# tricorder-teensy-mk-1_12_2.net
KiCad netlist of a schematic drawn in EAGLE
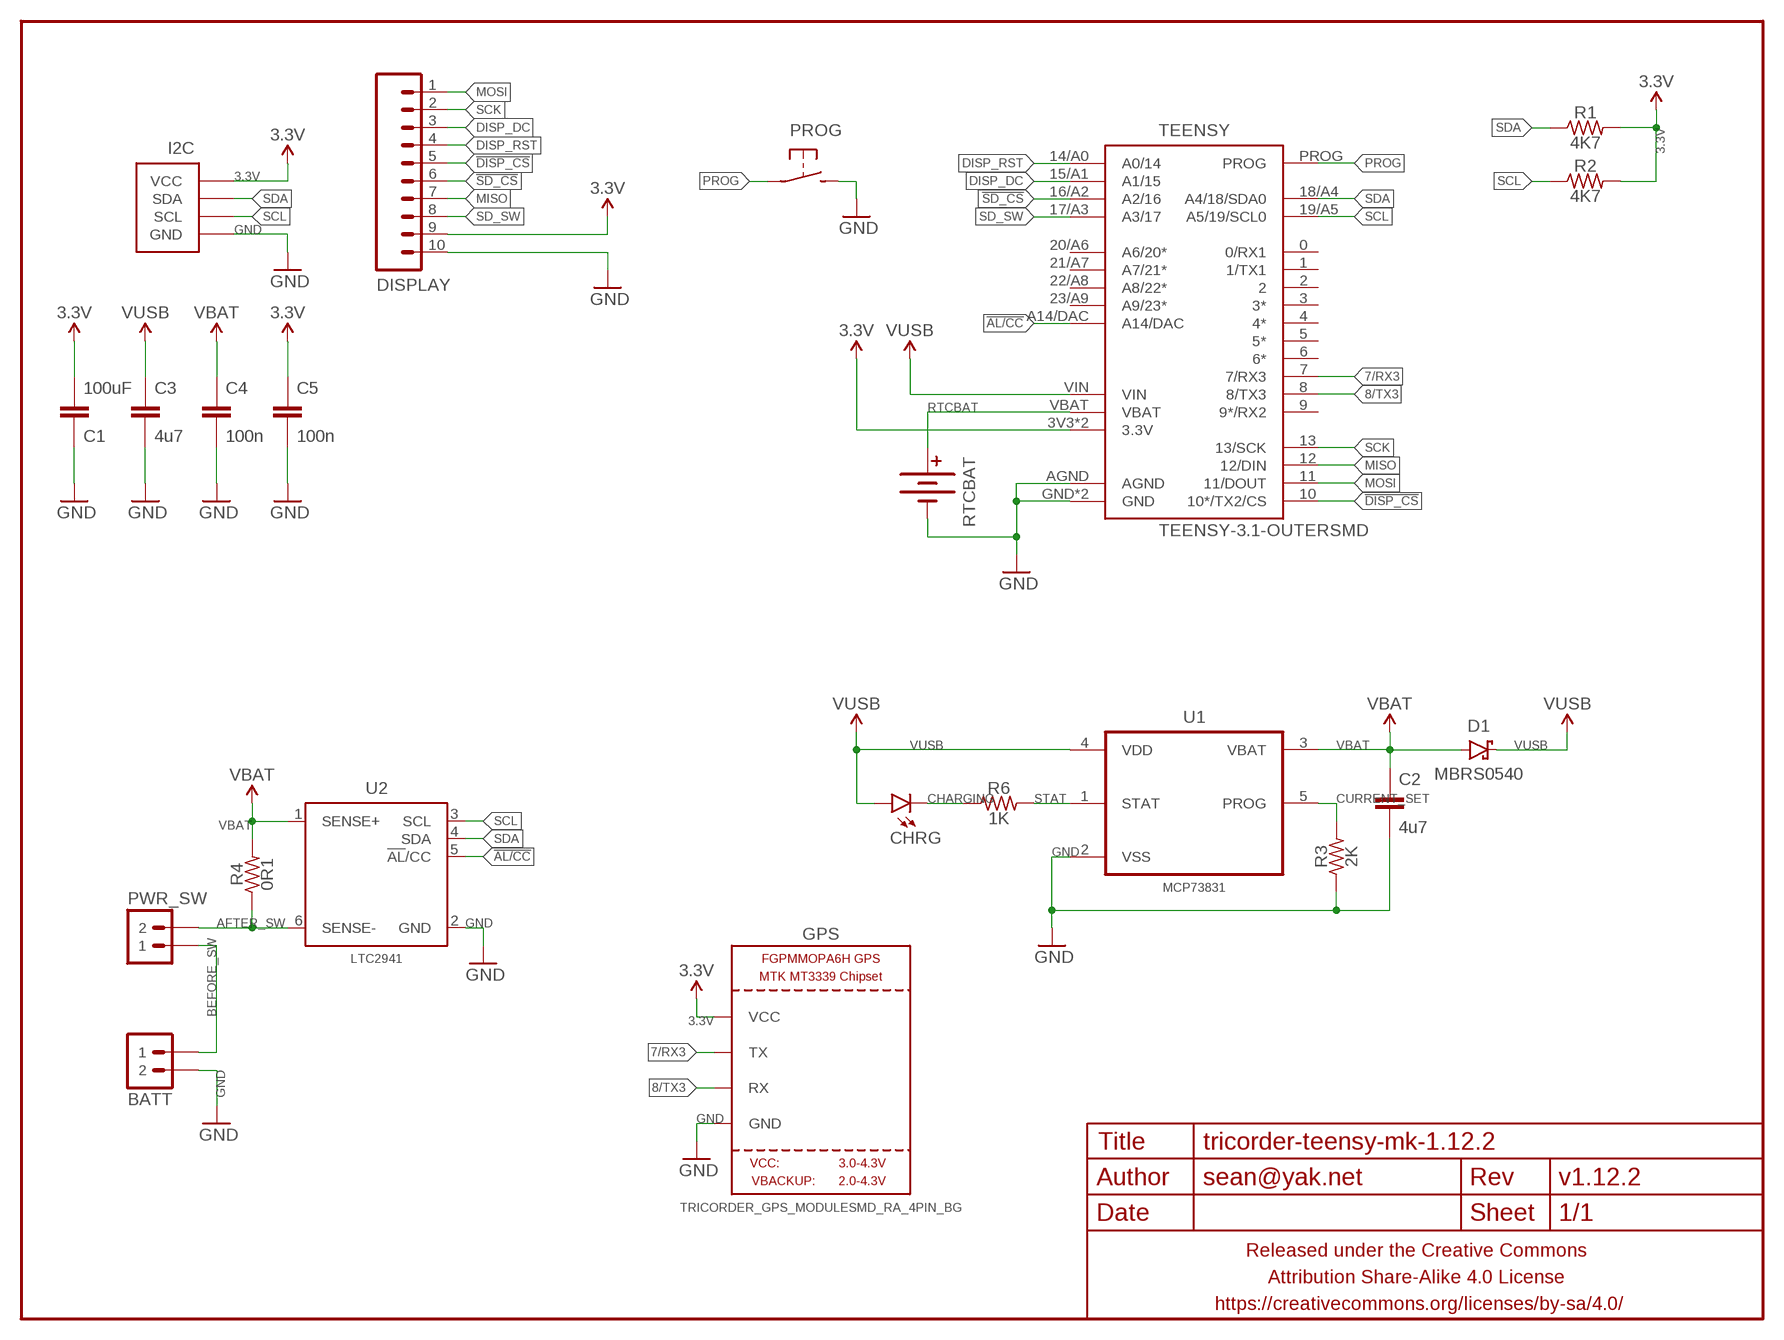
[diagram p0: schematic, sheet 1]

(export (version "E")
  (design (tool "Eeschema 10.0.6"))
  (components
    (comp (ref "BATT")
      (value "M02JST-2MM-SMT")
      (footprint "eagle-import:JST-2-SMD")
      (libsource (lib "eagle-import") (part "M02JST-2MM-SMT"))
    )
    (comp (ref "C1")
      (value "100uF")
      (footprint "eagle-import:C1210")
      (libsource (lib "eagle-import") (part "CAPACITOR-CERAMICC1210"))
    )
    (comp (ref "C2")
      (value "4u7")
      (footprint "eagle-import:C0603-TIGHTER")
      (libsource (lib "eagle-import") (part "CAPACITOR-CERAMICC0603-TIGHTER"))
    )
    (comp (ref "C3")
      (value "4u7")
      (footprint "eagle-import:C0603-TIGHTER")
      (libsource (lib "eagle-import") (part "CAPACITOR-CERAMICC0603-TIGHTER"))
    )
    (comp (ref "C4")
      (value "100n")
      (footprint "eagle-import:C0603-TIGHTER")
      (libsource (lib "eagle-import") (part "CAPACITOR-CERAMICC0603-TIGHTER"))
    )
    (comp (ref "C5")
      (value "100n")
      (footprint "eagle-import:C0603-TIGHTER")
      (libsource (lib "eagle-import") (part "CAPACITOR-CERAMICC0603-TIGHTER"))
    )
    (comp (ref "CHRG")
      (value "LED0603-TIGHT")
      (footprint "eagle-import:LED-0603-TIGHT")
      (libsource (lib "eagle-import") (part "LED0603-TIGHT"))
    )
    (comp (ref "D1")
      (value "MBRS0540")
      (footprint "eagle-import:SOD123-SCHOTTKY")
      (libsource (lib "eagle-import") (part "DIODE-SCHOTTKYSOD123"))
    )
    (comp (ref "DISPLAY")
      (value "M10SMD_RA_2MM")
      (footprint "eagle-import:1X10_SMD_RA_MALE")
      (libsource (lib "eagle-import") (part "M10SMD_RA_2MM"))
    )
    (comp (ref "FRAME1")
      (value "FRAME-LETTERNO_PACKAGE")
      (footprint "eagle-import:DUMMY")
      (fields
        (field (name "DESIGNER") "sean@yak.net")
        (field (name "VERSION") "v1.12.2")
        (field (name "DESIGNER_1") "sean@yak.net")
        (field (name "VERSION_1") "v1.12.2")
      )
      (libsource (lib "eagle-import") (part "FRAME-LETTERNO_PACKAGE"))
    )
    (comp (ref "GPS")
      (value "TRICORDER_GPS_MODULESMD_RA_4PIN_BG")
      (footprint "eagle-import:TRICORDER_GPS_MODULE_RA_CONN_SMD_4PIN_BG")
      (libsource (lib "eagle-import") (part "TRICORDER_GPS_MODULESMD_RA_4PIN_BG"))
    )
    (comp (ref "I2C")
      (value "M04-I2CSMD_2MM_RA")
      (footprint "eagle-import:1X04_SMD_RA_2MM_I2C")
      (libsource (lib "eagle-import") (part "M04-I2CSMD_2MM_RA"))
    )
    (comp (ref "PROG")
      (value "SPST-NO-TACTCK-PTS840-GK")
      (footprint "eagle-import:TACTILE-SMD-CK-PTS840-GK")
      (libsource (lib "eagle-import") (part "SPST-NO-TACTCK-PTS840-GK"))
    )
    (comp (ref "PWR_SW")
      (value "M02JST-2MM-SMT")
      (footprint "eagle-import:JST-2-SMD")
      (libsource (lib "eagle-import") (part "M02JST-2MM-SMT"))
    )
    (comp (ref "R1")
      (value "4K7")
      (footprint "eagle-import:R0603-TIGHTER")
      (libsource (lib "eagle-import") (part "RESISTORR0603-TIGHTER"))
    )
    (comp (ref "R2")
      (value "4K7")
      (footprint "eagle-import:R0603-TIGHTER")
      (libsource (lib "eagle-import") (part "RESISTORR0603-TIGHTER"))
    )
    (comp (ref "R3")
      (value "2K")
      (footprint "eagle-import:R0603-TIGHTER")
      (libsource (lib "eagle-import") (part "RESISTORR0603-TIGHTER"))
    )
    (comp (ref "R4")
      (value "0R1")
      (footprint "eagle-import:R0805-TIGHTER")
      (libsource (lib "eagle-import") (part "RESISTORR0805-TIGHTER"))
    )
    (comp (ref "R6")
      (value "1K")
      (footprint "eagle-import:R0603-TIGHTER")
      (libsource (lib "eagle-import") (part "RESISTORR0603-TIGHTER"))
    )
    (comp (ref "RTCBAT")
      (value "BATTERYML414")
      (footprint "eagle-import:BATTCON_4.8MM")
      (libsource (lib "eagle-import") (part "BATTERYML414"))
    )
    (comp (ref "TEENSY")
      (value "TEENSY-3.1-OUTERSMD")
      (footprint "eagle-import:TEENSY-3.1_SMT_BOTTOM_OUTERONLY")
      (libsource (lib "eagle-import") (part "TEENSY-3.1-OUTERSMD"))
    )
    (comp (ref "U1")
      (value "MCP73831")
      (footprint "eagle-import:SOT95P280X145-5N")
      (fields (field (name "MPN") "MCP73831T-2ACI/OT"))
      (libsource (lib "eagle-import") (part "MCP73831T-2ACI/OT"))
    )
    (comp (ref "U2")
      (value "LTC2941")
      (footprint "eagle-import:DFN200X300X50-7N")
      (libsource (lib "eagle-import") (part "LTC2941/2DCB"))
    )
  )
  (nets
    (net (code "1") (name "/AFTER_SW") (class "Default")
      (node (ref "PWR_SW") (pin "1") (pinfunction "2_1") (pintype "passive"))
      (node (ref "R4") (pin "1") (pinfunction "1_1") (pintype "passive"))
      (node (ref "U2") (pin "6") (pinfunction "SENSE-_6") (pintype "bidirectional"))
    )
    (net (code "2") (name "/BEFORE_SW") (class "Default")
      (node (ref "BATT") (pin "2") (pinfunction "1_2") (pintype "passive"))
      (node (ref "PWR_SW") (pin "2") (pinfunction "1_2") (pintype "passive"))
    )
    (net (code "3") (name "/CHARGING") (class "Default")
      (node (ref "CHRG") (pin "C") (pinfunction "C_C") (pintype "passive"))
      (node (ref "R6") (pin "1") (pinfunction "1_1") (pintype "passive"))
    )
    (net (code "4") (name "/CURRENT_SET") (class "Default")
      (node (ref "R3") (pin "2") (pinfunction "2_2") (pintype "passive"))
      (node (ref "U1") (pin "5") (pinfunction "PROG_5") (pintype "input"))
    )
    (net (code "5") (name "/RTCBAT") (class "Default")
      (node (ref "RTCBAT") (pin "A1") (pinfunction "+_A1") (pintype "power_in"))
      (node (ref "RTCBAT") (pin "A2") (pinfunction "+_A2") (pintype "power_in"))
      (node (ref "TEENSY") (pin "VBAT") (pinfunction "VBAT_VBAT") (pintype "bidirectional"))
    )
    (net (code "6") (name "/STAT") (class "Default")
      (node (ref "R6") (pin "2") (pinfunction "2_2") (pintype "passive"))
      (node (ref "U1") (pin "1") (pinfunction "STAT_1") (pintype "output"))
    )
    (net (code "7") (name "/~{AL{slash}CC}") (class "Default")
      (node (ref "TEENSY") (pin "A14/DAC") (pinfunction "A14/DAC_A14/DAC") (pintype "bidirectional"))
      (node (ref "U2") (pin "5") (pinfunction "~{AL}/CC_5") (pintype "bidirectional"))
    )
    (net (code "8") (name "/~{DISP_CS}") (class "Default")
      (node (ref "DISPLAY") (pin "5") (pinfunction "5_5") (pintype "passive"))
      (node (ref "TEENSY") (pin "10") (pinfunction "10*/TX2/CS_10") (pintype "bidirectional"))
    )
    (net (code "9") (name "/~{SD_CS}") (class "Default")
      (node (ref "DISPLAY") (pin "6") (pinfunction "6_6") (pintype "passive"))
      (node (ref "TEENSY") (pin "16/A2") (pinfunction "A2/16_16/A2") (pintype "bidirectional"))
    )
    (net (code "10") (name "3.3V") (class "Default")
      (node (ref "C1") (pin "2") (pinfunction "2_2") (pintype "passive"))
      (node (ref "C5") (pin "1") (pinfunction "1_1") (pintype "passive"))
      (node (ref "DISPLAY") (pin "9") (pinfunction "9_9") (pintype "passive"))
      (node (ref "GPS") (pin "VCC") (pinfunction "VCC_VCC") (pintype "bidirectional"))
      (node (ref "I2C") (pin "VCC") (pinfunction "VCC_VCC") (pintype "bidirectional"))
      (node (ref "R1") (pin "2") (pinfunction "2_2") (pintype "passive"))
      (node (ref "R2") (pin "2") (pinfunction "2_2") (pintype "passive"))
      (node (ref "TEENSY") (pin "3V3") (pinfunction "3.3V_3V3") (pintype "bidirectional"))
      (node (ref "TEENSY") (pin "3V3@1") (pinfunction "3.3V_3V3@1") (pintype "bidirectional"))
    )
    (net (code "11") (name "7{slash}RX3") (class "Default")
      (node (ref "GPS") (pin "TX") (pinfunction "TX_TX") (pintype "bidirectional"))
      (node (ref "TEENSY") (pin "7") (pinfunction "7/RX3_7") (pintype "bidirectional"))
    )
    (net (code "12") (name "8{slash}TX3") (class "Default")
      (node (ref "GPS") (pin "RX") (pinfunction "RX_RX") (pintype "bidirectional"))
      (node (ref "TEENSY") (pin "8") (pinfunction "8/TX3_8") (pintype "bidirectional"))
    )
    (net (code "13") (name "DISP_DC") (class "Default")
      (node (ref "DISPLAY") (pin "3") (pinfunction "3_3") (pintype "passive"))
      (node (ref "TEENSY") (pin "15/A1") (pinfunction "A1/15_15/A1") (pintype "bidirectional"))
    )
    (net (code "14") (name "DISP_RST") (class "Default")
      (node (ref "DISPLAY") (pin "4") (pinfunction "4_4") (pintype "passive"))
      (node (ref "TEENSY") (pin "14/A0") (pinfunction "A0/14_14/A0") (pintype "bidirectional"))
    )
    (net (code "15") (name "GND") (class "Default")
      (node (ref "BATT") (pin "1") (pinfunction "2_1") (pintype "passive"))
      (node (ref "C1") (pin "1") (pinfunction "1_1") (pintype "passive"))
      (node (ref "C2") (pin "2") (pinfunction "2_2") (pintype "passive"))
      (node (ref "C3") (pin "2") (pinfunction "2_2") (pintype "passive"))
      (node (ref "C4") (pin "2") (pinfunction "2_2") (pintype "passive"))
      (node (ref "C5") (pin "2") (pinfunction "2_2") (pintype "passive"))
      (node (ref "DISPLAY") (pin "10") (pinfunction "10_10") (pintype "passive"))
      (node (ref "GPS") (pin "GND") (pinfunction "GND_GND") (pintype "bidirectional"))
      (node (ref "I2C") (pin "GND") (pinfunction "GND_GND") (pintype "bidirectional"))
      (node (ref "PROG") (pin "3") (pinfunction "2_3") (pintype "passive"))
      (node (ref "PROG") (pin "4") (pinfunction "2_4") (pintype "passive"))
      (node (ref "R3") (pin "1") (pinfunction "1_1") (pintype "passive"))
      (node (ref "RTCBAT") (pin "-") (pinfunction "-_-") (pintype "power_in"))
      (node (ref "TEENSY") (pin "AGND") (pinfunction "AGND_AGND") (pintype "bidirectional"))
      (node (ref "TEENSY") (pin "GND") (pinfunction "GND_GND") (pintype "bidirectional"))
      (node (ref "TEENSY") (pin "GND@1") (pinfunction "GND_GND@1") (pintype "bidirectional"))
      (node (ref "U1") (pin "2") (pinfunction "VSS_2") (pintype "power_in"))
      (node (ref "U2") (pin "2") (pinfunction "GND_2") (pintype "bidirectional"))
    )
    (net (code "16") (name "MISO") (class "Default")
      (node (ref "DISPLAY") (pin "7") (pinfunction "7_7") (pintype "passive"))
      (node (ref "TEENSY") (pin "12") (pinfunction "12/DIN_12") (pintype "bidirectional"))
    )
    (net (code "17") (name "MOSI") (class "Default")
      (node (ref "DISPLAY") (pin "1") (pinfunction "1_1") (pintype "passive"))
      (node (ref "TEENSY") (pin "11") (pinfunction "11/DOUT_11") (pintype "bidirectional"))
    )
    (net (code "18") (name "PROG") (class "Default")
      (node (ref "PROG") (pin "1") (pinfunction "1_1") (pintype "passive"))
      (node (ref "PROG") (pin "2") (pinfunction "1_2") (pintype "passive"))
      (node (ref "TEENSY") (pin "PROG") (pinfunction "PROG_PROG") (pintype "bidirectional"))
    )
    (net (code "19") (name "SCK") (class "Default")
      (node (ref "DISPLAY") (pin "2") (pinfunction "2_2") (pintype "passive"))
      (node (ref "TEENSY") (pin "13") (pinfunction "13/SCK_13") (pintype "bidirectional"))
    )
    (net (code "20") (name "SCL") (class "Default")
      (node (ref "I2C") (pin "SCL") (pinfunction "SCL_SCL") (pintype "bidirectional"))
      (node (ref "R2") (pin "1") (pinfunction "1_1") (pintype "passive"))
      (node (ref "TEENSY") (pin "19/A5") (pinfunction "A5/19/SCL0_19/A5") (pintype "bidirectional"))
      (node (ref "U2") (pin "3") (pinfunction "SCL_3") (pintype "bidirectional"))
    )
    (net (code "21") (name "SDA") (class "Default")
      (node (ref "I2C") (pin "SDA") (pinfunction "SDA_SDA") (pintype "bidirectional"))
      (node (ref "R1") (pin "1") (pinfunction "1_1") (pintype "passive"))
      (node (ref "TEENSY") (pin "18/A4") (pinfunction "A4/18/SDA0_18/A4") (pintype "bidirectional"))
      (node (ref "U2") (pin "4") (pinfunction "SDA_4") (pintype "bidirectional"))
    )
    (net (code "22") (name "SD_SW") (class "Default")
      (node (ref "DISPLAY") (pin "8") (pinfunction "8_8") (pintype "passive"))
      (node (ref "TEENSY") (pin "17/A3") (pinfunction "A3/17_17/A3") (pintype "bidirectional"))
    )
    (net (code "23") (name "VBAT") (class "Default")
      (node (ref "C2") (pin "1") (pinfunction "1_1") (pintype "passive"))
      (node (ref "C4") (pin "1") (pinfunction "1_1") (pintype "passive"))
      (node (ref "D1") (pin "A") (pinfunction "A_A") (pintype "passive"))
      (node (ref "R4") (pin "2") (pinfunction "2_2") (pintype "passive"))
      (node (ref "U1") (pin "3") (pinfunction "VBAT_3") (pintype "output"))
      (node (ref "U2") (pin "1") (pinfunction "SENSE+_1") (pintype "bidirectional"))
    )
    (net (code "24") (name "VUSB") (class "Default")
      (node (ref "C3") (pin "1") (pinfunction "1_1") (pintype "passive"))
      (node (ref "CHRG") (pin "A") (pinfunction "A_A") (pintype "passive"))
      (node (ref "D1") (pin "C") (pinfunction "C_C") (pintype "passive"))
      (node (ref "TEENSY") (pin "VIN") (pinfunction "VIN_VIN") (pintype "bidirectional"))
      (node (ref "U1") (pin "4") (pinfunction "VDD_4") (pintype "power_in"))
    )
    (net (code "25") (name "unconnected-(TEENSY-0{slash}RX1-Pad0)") (class "Default")
      (node (ref "TEENSY") (pin "0") (pinfunction "0/RX1_0") (pintype "bidirectional"))
    )
    (net (code "26") (name "unconnected-(TEENSY-1{slash}TX1-Pad1)") (class "Default")
      (node (ref "TEENSY") (pin "1") (pinfunction "1/TX1_1") (pintype "bidirectional"))
    )
    (net (code "27") (name "unconnected-(TEENSY-3*-Pad3)") (class "Default")
      (node (ref "TEENSY") (pin "3") (pinfunction "3*_3") (pintype "bidirectional"))
    )
    (net (code "28") (name "unconnected-(TEENSY-4*-Pad4)") (class "Default")
      (node (ref "TEENSY") (pin "4") (pinfunction "4*_4") (pintype "bidirectional"))
    )
    (net (code "29") (name "unconnected-(TEENSY-5*-Pad5)") (class "Default")
      (node (ref "TEENSY") (pin "5") (pinfunction "5*_5") (pintype "bidirectional"))
    )
    (net (code "30") (name "unconnected-(TEENSY-6*-Pad6)") (class "Default")
      (node (ref "TEENSY") (pin "6") (pinfunction "6*_6") (pintype "bidirectional"))
    )
    (net (code "31") (name "unconnected-(TEENSY-9*{slash}RX2-Pad9)") (class "Default")
      (node (ref "TEENSY") (pin "9") (pinfunction "9*/RX2_9") (pintype "bidirectional"))
    )
    (net (code "32") (name "unconnected-(TEENSY-A6{slash}20*-Pad20{slash}A6)") (class "Default")
      (node (ref "TEENSY") (pin "20/A6") (pinfunction "A6/20*_20/A6") (pintype "bidirectional"))
    )
    (net (code "33") (name "unconnected-(TEENSY-A7{slash}21*-Pad21{slash}A7)") (class "Default")
      (node (ref "TEENSY") (pin "21/A7") (pinfunction "A7/21*_21/A7") (pintype "bidirectional"))
    )
    (net (code "34") (name "unconnected-(TEENSY-A8{slash}22*-Pad22{slash}A8)") (class "Default")
      (node (ref "TEENSY") (pin "22/A8") (pinfunction "A8/22*_22/A8") (pintype "bidirectional"))
    )
    (net (code "35") (name "unconnected-(TEENSY-A9{slash}23*-Pad23{slash}A9)") (class "Default")
      (node (ref "TEENSY") (pin "23/A9") (pinfunction "A9/23*_23/A9") (pintype "bidirectional"))
    )
    (net (code "36") (name "unconnected-(TEENSY-Pad2)") (class "Default")
      (node (ref "TEENSY") (pin "2") (pinfunction "2_2") (pintype "bidirectional"))
    )
  )
)
